# Connections.net
KiCad netlist of a schematic drawn in Altium Designer
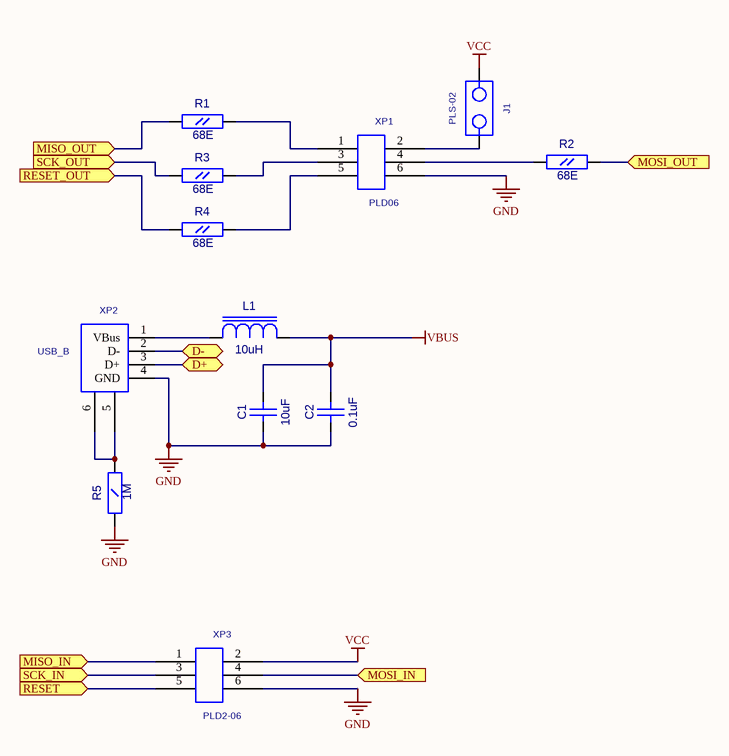
[diagram p0: Connections.SchDoc]

(export (version "E")
  (design (tool "Eeschema 10.0.6"))
  (components
    (comp (ref "C1")
      (value "10uF")
      (footprint "CC0805")
      (description "CC0805")
      (libsource (lib "gprs_modem_2") (part "CC0805"))
    )
    (comp (ref "C2")
      (value "0.1uF")
      (footprint "CC0603")
      (description "CC0603")
      (libsource (lib "gprs_modem_2") (part "CC0603"))
    )
    (comp (ref "J1") (value "PLS-02") (footprint "PLS-02") (libsource (lib "gprs_modem_2") (part "PLS-02")))
    (comp (ref "L1")
      (value "10uH")
      (footprint "RC0805")
      (description "L0805")
      (libsource (lib "gprs_modem_2") (part "L0805"))
    )
    (comp (ref "R1")
      (value "68E")
      (footprint "RC0603")
      (description "RC0603")
      (libsource (lib "gprs_modem_2") (part "RC0603"))
    )
    (comp (ref "R2")
      (value "68E")
      (footprint "RC0603")
      (description "RC0603")
      (libsource (lib "gprs_modem_2") (part "RC0603"))
    )
    (comp (ref "R3")
      (value "68E")
      (footprint "RC0603")
      (description "RC0603")
      (libsource (lib "gprs_modem_2") (part "RC0603"))
    )
    (comp (ref "R4")
      (value "68E")
      (footprint "RC0603")
      (description "RC0603")
      (libsource (lib "gprs_modem_2") (part "RC0603"))
    )
    (comp (ref "R5")
      (value "1M")
      (footprint "RC1206")
      (description "RC1206")
      (libsource (lib "gprs_modem_2") (part "RC1206"))
    )
    (comp (ref "XP1") (value "PLD06") (footprint "PIN6") (libsource (lib "gprs_modem_2") (part "PLD06")))
    (comp (ref "XP2") (value "USB_B") (footprint "USB-B") (libsource (lib "gprs_modem_2") (part "USB_B")))
    (comp (ref "XP3")
      (value "PLD2-06")
      (footprint "PLD2-06")
      (libsource (lib "gprs_modem_2") (part "PLD2-06"))
    )
  )
  (nets
    (net (code "1") (name "/D+") (class "Default")
      (node (ref "XP2") (pin "3") (pinfunction "D+_3") (pintype "passive"))
    )
    (net (code "2") (name "/D-") (class "Default")
      (node (ref "XP2") (pin "2") (pinfunction "D-_2") (pintype "passive"))
    )
    (net (code "3") (name "/MISO_IN") (class "Default") (node (ref "XP3") (pin "1") (pintype "passive")))
    (net (code "4") (name "/MISO_OUT") (class "Default")
      (node (ref "R1") (pin "1") (pinfunction "A_1") (pintype "passive"))
    )
    (net (code "5") (name "/MOSI_IN") (class "Default") (node (ref "XP3") (pin "4") (pintype "passive")))
    (net (code "6") (name "/MOSI_OUT") (class "Default")
      (node (ref "R2") (pin "2") (pinfunction "B_2") (pintype "passive"))
    )
    (net (code "7") (name "/RESET") (class "Default") (node (ref "XP3") (pin "5") (pintype "passive")))
    (net (code "8") (name "/RESET_OUT") (class "Default")
      (node (ref "R4") (pin "1") (pinfunction "A_1") (pintype "passive"))
    )
    (net (code "9") (name "/SCK_IN") (class "Default") (node (ref "XP3") (pin "3") (pintype "passive")))
    (net (code "10") (name "/SCK_OUT") (class "Default")
      (node (ref "R3") (pin "1") (pinfunction "A_1") (pintype "passive"))
    )
    (net (code "11") (name "GND") (class "Default")
      (node (ref "C1") (pin "1") (pinfunction "A_1") (pintype "passive"))
      (node (ref "C2") (pin "1") (pinfunction "A_1") (pintype "passive"))
      (node (ref "R5") (pin "1") (pinfunction "A_1") (pintype "passive"))
      (node (ref "XP1") (pin "6") (pintype "passive"))
      (node (ref "XP2") (pin "4") (pinfunction "GND_4") (pintype "passive"))
      (node (ref "XP3") (pin "6") (pintype "passive"))
    )
    (net (code "12") (name "Net-(J1-Pad2)") (class "Default")
      (node (ref "J1") (pin "2") (pintype "passive"))
      (node (ref "XP1") (pin "2") (pintype "passive"))
    )
    (net (code "13") (name "Net-(L1-A)") (class "Default")
      (node (ref "L1") (pin "1") (pinfunction "A_1") (pintype "passive"))
      (node (ref "XP2") (pin "1") (pinfunction "VBus_1") (pintype "passive"))
    )
    (net (code "14") (name "Net-(R1-B)") (class "Default")
      (node (ref "R1") (pin "2") (pinfunction "B_2") (pintype "passive"))
      (node (ref "XP1") (pin "1") (pintype "passive"))
    )
    (net (code "15") (name "Net-(R2-A)") (class "Default")
      (node (ref "R2") (pin "1") (pinfunction "A_1") (pintype "passive"))
      (node (ref "XP1") (pin "4") (pintype "passive"))
    )
    (net (code "16") (name "Net-(R3-B)") (class "Default")
      (node (ref "R3") (pin "2") (pinfunction "B_2") (pintype "passive"))
      (node (ref "XP1") (pin "3") (pintype "passive"))
    )
    (net (code "17") (name "Net-(R4-B)") (class "Default")
      (node (ref "R4") (pin "2") (pinfunction "B_2") (pintype "passive"))
      (node (ref "XP1") (pin "5") (pintype "passive"))
    )
    (net (code "18") (name "Net-(R5-B)") (class "Default")
      (node (ref "R5") (pin "2") (pinfunction "B_2") (pintype "passive"))
      (node (ref "XP2") (pin "5") (pintype "passive"))
      (node (ref "XP2") (pin "6") (pintype "passive"))
    )
    (net (code "19") (name "VBUS") (class "Default")
      (node (ref "C1") (pin "2") (pinfunction "B_2") (pintype "passive"))
      (node (ref "C2") (pin "2") (pinfunction "B_2") (pintype "passive"))
      (node (ref "L1") (pin "2") (pinfunction "B_2") (pintype "passive"))
    )
    (net (code "20") (name "VCC") (class "Default")
      (node (ref "J1") (pin "1") (pintype "passive"))
      (node (ref "XP3") (pin "2") (pintype "passive"))
    )
  )
)
